# Accelerometer.net
KiCad netlist of a schematic drawn in Altium Designer
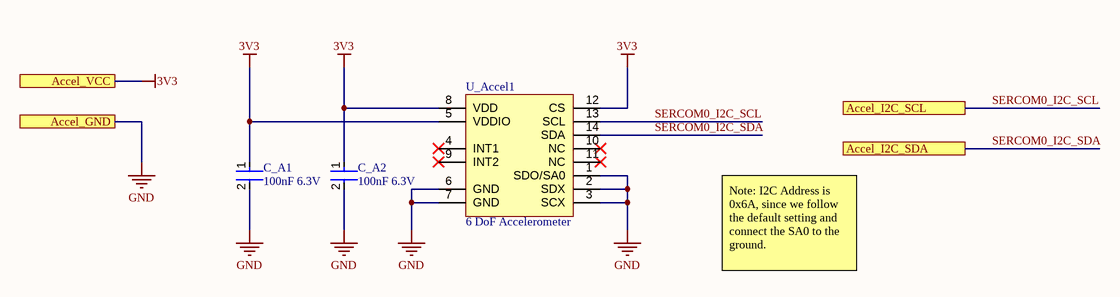
[diagram p0: Accelerometer.SchDoc]

(export (version "E")
  (design (tool "Eeschema 10.0.6"))
  (components
    (comp (ref "C_A1")
      (value "100nF 6.3V")
      (footprint "FP-GRM033-0_03-IPC_A")
      (description "Chip Multilayer Ceramic Capacitors for General Purpose, 0201, 0.10uF, X6S, 22%, 20%, 6.3V")
      (fields (field (name "TOLERANCE") "20%"))
      (libsource (lib "Altium Content Vault") (part "b4654b650e69147ec39a6b967a45e02"))
    )
    (comp (ref "C_A2")
      (value "100nF 6.3V")
      (footprint "FP-GRM033-0_03-IPC_A")
      (description "Chip Multilayer Ceramic Capacitors for General Purpose, 0201, 0.10uF, X6S, 22%, 20%, 6.3V")
      (fields (field (name "TOLERANCE") "20%"))
      (libsource (lib "Altium Content Vault") (part "b4654b650e69147ec39a6b967a45e02"))
    )
    (comp (ref "U_Accel1")
      (value "6 DoF Accelerometer")
      (footprint "LSM6DSO:LSM6DSO")
      (description "Accelerometer and 3D Gyroscope 3D Always-On 1.71V to 3.6V 0.55mA 14-Pin LGA T/R")
      (fields
        (field (name "MANUFACTURER") "STMicroelectronics")
        (field (name "MANUFACTURER PART NUMBER") "LSM6DSO32TR")
      )
      (libsource (lib "LSM6DSO") (part "LSM6DSO32TR"))
    )
  )
  (nets
    (net (code "1") (name "/SERCOM0_I2C_SCL") (class "Default")
      (node (ref "U_Accel1") (pin "13") (pinfunction "SCL_13") (pintype "passive"))
    )
    (net (code "2") (name "/SERCOM0_I2C_SDA") (class "Default")
      (node (ref "U_Accel1") (pin "14") (pinfunction "SDA_14") (pintype "passive"))
    )
    (net (code "3") (name "3V3") (class "Default")
      (node (ref "C_A1") (pin "1") (pinfunction "1_1") (pintype "passive"))
      (node (ref "C_A2") (pin "1") (pinfunction "1_1") (pintype "passive"))
      (node (ref "U_Accel1") (pin "12") (pinfunction "CS_12") (pintype "passive"))
      (node (ref "U_Accel1") (pin "5") (pinfunction "VDDIO_5") (pintype "passive"))
      (node (ref "U_Accel1") (pin "8") (pinfunction "VDD_8") (pintype "passive"))
    )
    (net (code "4") (name "GND") (class "Default")
      (node (ref "C_A1") (pin "2") (pinfunction "2_2") (pintype "passive"))
      (node (ref "C_A2") (pin "2") (pinfunction "2_2") (pintype "passive"))
      (node (ref "U_Accel1") (pin "1") (pinfunction "SDO/SA0_1") (pintype "passive"))
      (node (ref "U_Accel1") (pin "2") (pinfunction "SDX_2") (pintype "passive"))
      (node (ref "U_Accel1") (pin "3") (pinfunction "SCX_3") (pintype "passive"))
      (node (ref "U_Accel1") (pin "6") (pinfunction "GND_6") (pintype "passive"))
      (node (ref "U_Accel1") (pin "7") (pinfunction "GND_7") (pintype "passive"))
    )
    (net (code "5") (name "unconnected-(U_Accel1-INT1-Pad4)") (class "Default")
      (node (ref "U_Accel1") (pin "4") (pinfunction "INT1_4") (pintype "passive+no_connect"))
    )
    (net (code "6") (name "unconnected-(U_Accel1-INT2-Pad9)") (class "Default")
      (node (ref "U_Accel1") (pin "9") (pinfunction "INT2_9") (pintype "passive+no_connect"))
    )
    (net (code "7") (name "unconnected-(U_Accel1-NC-Pad10)") (class "Default")
      (node (ref "U_Accel1") (pin "10") (pinfunction "NC_10") (pintype "passive+no_connect"))
    )
    (net (code "8") (name "unconnected-(U_Accel1-NC-Pad11)") (class "Default")
      (node (ref "U_Accel1") (pin "11") (pinfunction "NC_11") (pintype "passive+no_connect"))
    )
  )
)
